# NES_IO_US_SNES_REV1_5.net
KiCad netlist of a schematic drawn in EAGLE
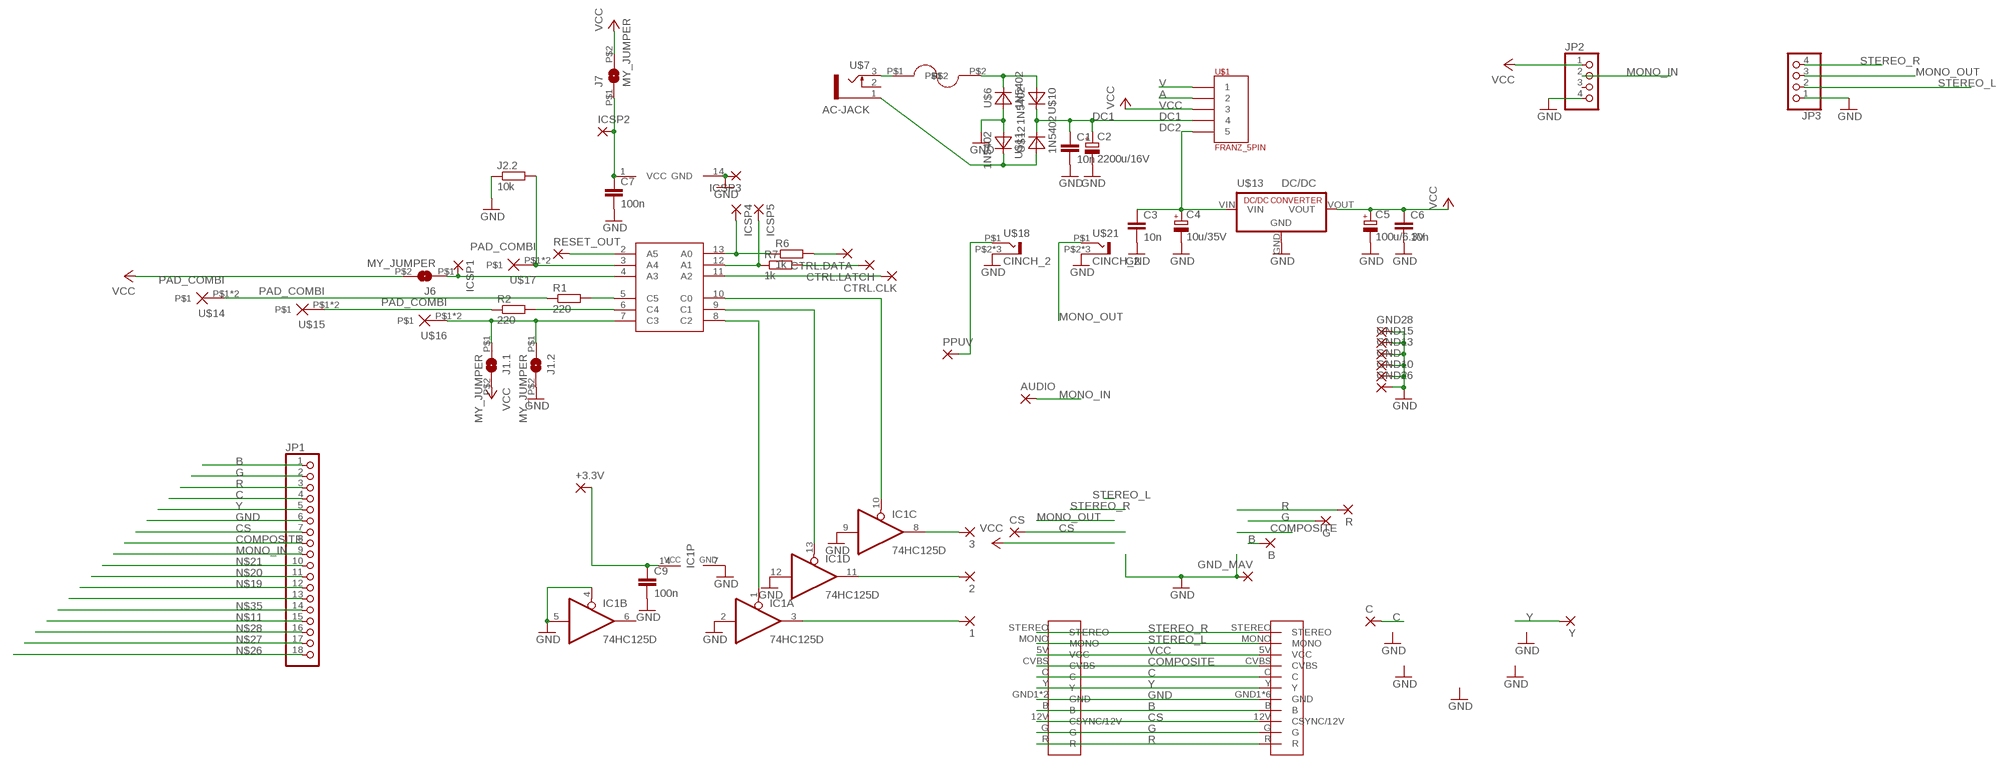
[diagram p0: schematic, sheet 1]

(export (version "E")
  (design (tool "Eeschema 10.0.6"))
  (components
    (comp (ref "+3.3V")
      (value "SMD2")
      (footprint "eagle-import:SMD1,27-2,54")
      (libsource (lib "eagle-import") (part "SMD2"))
    )
    (comp (ref "1")
      (value "SMD2")
      (footprint "eagle-import:SMD1,27-2,54")
      (libsource (lib "eagle-import") (part "SMD2"))
    )
    (comp (ref "2")
      (value "SMD2")
      (footprint "eagle-import:SMD1,27-2,54")
      (libsource (lib "eagle-import") (part "SMD2"))
    )
    (comp (ref "3")
      (value "SMD2")
      (footprint "eagle-import:SMD1,27-2,54")
      (libsource (lib "eagle-import") (part "SMD2"))
    )
    (comp (ref "AUDIO")
      (value "SMD2")
      (footprint "eagle-import:SMD1,27-2,54")
      (libsource (lib "eagle-import") (part "SMD2"))
    )
    (comp (ref "B")
      (value "SMD2")
      (footprint "eagle-import:SMD1,27-2,54")
      (libsource (lib "eagle-import") (part "SMD2"))
    )
    (comp (ref "C")
      (value "SMD2")
      (footprint "eagle-import:SMD1,27-2,54")
      (libsource (lib "eagle-import") (part "SMD2"))
    )
    (comp (ref "C1")
      (value "10n")
      (footprint "eagle-import:Z0805")
      (libsource (lib "eagle-import") (part "C0805"))
    )
    (comp (ref "C2")
      (value "2200u/16V")
      (footprint "eagle-import:E5-13")
      (libsource (lib "eagle-import") (part "resistor_CPOL-EUE5-13"))
    )
    (comp (ref "C3")
      (value "10n")
      (footprint "eagle-import:Z0805")
      (libsource (lib "eagle-import") (part "C0805"))
    )
    (comp (ref "C4")
      (value "10u/35V")
      (footprint "eagle-import:PANASONIC_B")
      (libsource (lib "eagle-import") (part "CPOL-EUB"))
    )
    (comp (ref "C5")
      (value "100u/6.3V")
      (footprint "eagle-import:PANASONIC_D")
      (libsource (lib "eagle-import") (part "CPOL-EUD"))
    )
    (comp (ref "C6")
      (value "10n")
      (footprint "eagle-import:Z0805")
      (libsource (lib "eagle-import") (part "C0805"))
    )
    (comp (ref "C7")
      (value "100n")
      (footprint "eagle-import:Z0805")
      (libsource (lib "eagle-import") (part "C0805"))
    )
    (comp (ref "C9")
      (value "100n")
      (footprint "eagle-import:Z0805")
      (libsource (lib "eagle-import") (part "C0805"))
    )
    (comp (ref "CS")
      (value "SMD2")
      (footprint "eagle-import:SMD1,27-2,54")
      (libsource (lib "eagle-import") (part "SMD2"))
    )
    (comp (ref "CTRL.CLK")
      (value "SMD2")
      (footprint "eagle-import:SMD1,27-2,54")
      (libsource (lib "eagle-import") (part "SMD2"))
    )
    (comp (ref "CTRL.DATA")
      (value "SMD2")
      (footprint "eagle-import:SMD1,27-2,54")
      (libsource (lib "eagle-import") (part "SMD2"))
    )
    (comp (ref "CTRL.LATCH")
      (value "SMD2")
      (footprint "eagle-import:SMD1,27-2,54")
      (libsource (lib "eagle-import") (part "SMD2"))
    )
    (comp (ref "G")
      (value "SMD2")
      (footprint "eagle-import:SMD1,27-2,54")
      (libsource (lib "eagle-import") (part "SMD2"))
    )
    (comp (ref "GND")
      (value "SMD5")
      (footprint "eagle-import:SMD2,54-5,08")
      (libsource (lib "eagle-import") (part "SMD5"))
    )
    (comp (ref "GND10")
      (value "SMD5")
      (footprint "eagle-import:SMD2,54-5,08")
      (libsource (lib "eagle-import") (part "SMD5"))
    )
    (comp (ref "GND13")
      (value "SMD5")
      (footprint "eagle-import:SMD2,54-5,08")
      (libsource (lib "eagle-import") (part "SMD5"))
    )
    (comp (ref "GND15")
      (value "SMD5")
      (footprint "eagle-import:SMD2,54-5,08")
      (libsource (lib "eagle-import") (part "SMD5"))
    )
    (comp (ref "GND26")
      (value "SMD5")
      (footprint "eagle-import:SMD2,54-5,08")
      (libsource (lib "eagle-import") (part "SMD5"))
    )
    (comp (ref "GND28")
      (value "SMD5")
      (footprint "eagle-import:SMD2,54-5,08")
      (libsource (lib "eagle-import") (part "SMD5"))
    )
    (comp (ref "GND_MAV")
      (value "SMD2")
      (footprint "eagle-import:SMD1,27-2,54")
      (libsource (lib "eagle-import") (part "SMD2"))
    )
    (comp (ref "IC1")
      (value "74HC125D")
      (footprint "eagle-import:SO14")
      (libsource (lib "eagle-import") (part "74125DHC"))
    )
    (comp (ref "ICSP1")
      (value "1,6/0,8")
      (footprint "eagle-import:1,6_0,8")
      (libsource (lib "eagle-import") (part "1,6/0,8"))
    )
    (comp (ref "ICSP2")
      (value "1,6/0,8")
      (footprint "eagle-import:1,6_0,8")
      (libsource (lib "eagle-import") (part "1,6/0,8"))
    )
    (comp (ref "ICSP3")
      (value "1,6/0,8")
      (footprint "eagle-import:1,6_0,8")
      (libsource (lib "eagle-import") (part "1,6/0,8"))
    )
    (comp (ref "ICSP4")
      (value "1,6/0,8")
      (footprint "eagle-import:1,6_0,8")
      (libsource (lib "eagle-import") (part "1,6/0,8"))
    )
    (comp (ref "ICSP5")
      (value "1,6/0,8")
      (footprint "eagle-import:1,6_0,8")
      (libsource (lib "eagle-import") (part "1,6/0,8"))
    )
    (comp (ref "J1.1")
      (value "MY_JUMPER")
      (footprint "eagle-import:MYJUMP")
      (libsource (lib "eagle-import") (part "MY_JUMPER"))
    )
    (comp (ref "J1.2")
      (value "MY_JUMPER")
      (footprint "eagle-import:MYJUMP")
      (libsource (lib "eagle-import") (part "MY_JUMPER"))
    )
    (comp (ref "J2.2")
      (value "10k")
      (footprint "eagle-import:Z0805")
      (libsource (lib "eagle-import") (part "R0805"))
    )
    (comp (ref "J6")
      (value "MY_JUMPER")
      (footprint "eagle-import:MYJUMP")
      (libsource (lib "eagle-import") (part "MY_JUMPER"))
    )
    (comp (ref "J7")
      (value "MY_JUMPER")
      (footprint "eagle-import:MYJUMP")
      (libsource (lib "eagle-import") (part "MY_JUMPER"))
    )
    (comp (ref "JP1")
      (value "PINHD-1X18_2.00")
      (footprint "eagle-import:1X18M")
      (libsource (lib "eagle-import") (part "PINHD-1X18_2.00"))
    )
    (comp (ref "JP2")
      (value "PINHD-1X04_2.54-S")
      (footprint "eagle-import:1X04-S")
      (libsource (lib "eagle-import") (part "PINHD-1X04_2.54-S"))
    )
    (comp (ref "JP3")
      (value "PINHD-1X04_2.54-S")
      (footprint "eagle-import:1X04-S")
      (libsource (lib "eagle-import") (part "PINHD-1X04_2.54-S"))
    )
    (comp (ref "PPUV")
      (value "SMD2")
      (footprint "eagle-import:SMD1,27-2,54")
      (libsource (lib "eagle-import") (part "SMD2"))
    )
    (comp (ref "R")
      (value "SMD2")
      (footprint "eagle-import:SMD1,27-2,54")
      (libsource (lib "eagle-import") (part "SMD2"))
    )
    (comp (ref "R1")
      (value "220")
      (footprint "eagle-import:Z0805")
      (libsource (lib "eagle-import") (part "R0805"))
    )
    (comp (ref "R2")
      (value "220")
      (footprint "eagle-import:Z0805")
      (libsource (lib "eagle-import") (part "R0805"))
    )
    (comp (ref "R6")
      (value "1k")
      (footprint "eagle-import:Z0805")
      (libsource (lib "eagle-import") (part "R0805"))
    )
    (comp (ref "R7")
      (value "1k")
      (footprint "eagle-import:Z0805")
      (libsource (lib "eagle-import") (part "R0805"))
    )
    (comp (ref "RESET_OUT")
      (value "SMD2")
      (footprint "eagle-import:SMD1,27-2,54")
      (libsource (lib "eagle-import") (part "SMD2"))
    )
    (comp (ref "U$1")
      (value "FRANZ_5PIN")
      (footprint "eagle-import:5X2.22RM4")
      (libsource (lib "eagle-import") (part "FRANZ_5PIN"))
    )
    (comp (ref "U$2")
      (value "FUSEHOLDER")
      (footprint "eagle-import:FUSEHOLDER")
      (libsource (lib "eagle-import") (part "FUSEHOLDER"))
    )
    (comp (ref "U$5")
      (value "PIC16F630_SIMPLE")
      (footprint "eagle-import:PIC16F630")
      (libsource (lib "eagle-import") (part "PIC16F630_SIMPLE"))
    )
    (comp (ref "U$6")
      (value "1N5402")
      (footprint "eagle-import:DO201")
      (libsource (lib "eagle-import") (part "1N5402"))
    )
    (comp (ref "U$7")
      (value "AC-JACK")
      (footprint "eagle-import:AC-JACK")
      (libsource (lib "eagle-import") (part "AC-JACK"))
    )
    (comp (ref "U$10")
      (value "1N5402")
      (footprint "eagle-import:DO201")
      (libsource (lib "eagle-import") (part "1N5402"))
    )
    (comp (ref "U$11")
      (value "1N5402")
      (footprint "eagle-import:DO201")
      (libsource (lib "eagle-import") (part "1N5402"))
    )
    (comp (ref "U$12")
      (value "1N5402")
      (footprint "eagle-import:DO201")
      (libsource (lib "eagle-import") (part "1N5402"))
    )
    (comp (ref "U$13")
      (value "DC/DC")
      (footprint "eagle-import:RECOM")
      (libsource (lib "eagle-import") (part "DC/DC"))
    )
    (comp (ref "U$14")
      (value "PAD_COMBI")
      (footprint "eagle-import:PAD_COMBI")
      (libsource (lib "eagle-import") (part "PAD_COMBI"))
    )
    (comp (ref "U$15")
      (value "PAD_COMBI")
      (footprint "eagle-import:PAD_COMBI")
      (libsource (lib "eagle-import") (part "PAD_COMBI"))
    )
    (comp (ref "U$16")
      (value "PAD_COMBI")
      (footprint "eagle-import:PAD_COMBI")
      (libsource (lib "eagle-import") (part "PAD_COMBI"))
    )
    (comp (ref "U$17")
      (value "PAD_COMBI")
      (footprint "eagle-import:PAD_COMBI")
      (libsource (lib "eagle-import") (part "PAD_COMBI"))
    )
    (comp (ref "U$18")
      (value "CINCH_2")
      (footprint "eagle-import:CINCH_2")
      (libsource (lib "eagle-import") (part "CINCH_2"))
    )
    (comp (ref "U$19")
      (value "GC-MULTIAV")
      (footprint "eagle-import:GC-MULTIAV")
      (libsource (lib "eagle-import") (part "GC-MULTIAV"))
    )
    (comp (ref "U$20")
      (value "SNES-MULTIAV2")
      (footprint "eagle-import:SNES-MULTIAV2")
      (libsource (lib "eagle-import") (part "SNES-MULTIAV2"))
    )
    (comp (ref "U$21")
      (value "CINCH_2")
      (footprint "eagle-import:CINCH_2")
      (libsource (lib "eagle-import") (part "CINCH_2"))
    )
    (comp (ref "Y")
      (value "SMD2")
      (footprint "eagle-import:SMD1,27-2,54")
      (libsource (lib "eagle-import") (part "SMD2"))
    )
  )
  (nets
    (net (code "1") (name "/A") (class "Default")
      (node (ref "U$1") (pin "P$2") (pinfunction "2_P$2") (pintype "bidirectional"))
    )
    (net (code "2") (name "/B") (class "Default")
      (node (ref "B") (pin "1") (pinfunction "P_1") (pintype "passive"))
      (node (ref "JP1") (pin "1") (pinfunction "1_1") (pintype "passive"))
      (node (ref "U$19") (pin "B") (pinfunction "B_B") (pintype "output"))
      (node (ref "U$20") (pin "B") (pinfunction "B_B") (pintype "output"))
    )
    (net (code "3") (name "/C") (class "Default")
      (node (ref "C") (pin "1") (pinfunction "P_1") (pintype "passive"))
      (node (ref "JP1") (pin "4") (pinfunction "4_4") (pintype "passive"))
      (node (ref "U$19") (pin "C") (pinfunction "C_C") (pintype "output"))
      (node (ref "U$20") (pin "C") (pinfunction "C_C") (pintype "output"))
    )
    (net (code "4") (name "/COMPOSITE") (class "Default")
      (node (ref "JP1") (pin "8") (pinfunction "8_8") (pintype "passive"))
      (node (ref "PPUV") (pin "1") (pinfunction "P_1") (pintype "passive"))
      (node (ref "U$18") (pin "P$1") (pinfunction "T_P$1") (pintype "passive"))
      (node (ref "U$19") (pin "CVBS") (pinfunction "CVBS_CVBS") (pintype "output"))
      (node (ref "U$20") (pin "CVBS") (pinfunction "CVBS_CVBS") (pintype "output"))
    )
    (net (code "5") (name "/CS") (class "Default")
      (node (ref "CS") (pin "1") (pinfunction "P_1") (pintype "passive"))
      (node (ref "JP1") (pin "7") (pinfunction "7_7") (pintype "passive"))
      (node (ref "U$19") (pin "12V") (pinfunction "CSYNC/12V_12V") (pintype "output"))
      (node (ref "U$20") (pin "12V") (pinfunction "CSYNC/12V_12V") (pintype "output"))
    )
    (net (code "6") (name "/DC1") (class "Default")
      (node (ref "C1") (pin "1") (pinfunction "1_1") (pintype "passive"))
      (node (ref "C2") (pin "+") (pinfunction "+_+") (pintype "passive"))
      (node (ref "U$1") (pin "P$4") (pinfunction "4_P$4") (pintype "bidirectional"))
      (node (ref "U$10") (pin "C") (pinfunction "C_C") (pintype "passive"))
      (node (ref "U$12") (pin "C") (pinfunction "C_C") (pintype "passive"))
    )
    (net (code "7") (name "/DC2") (class "Default")
      (node (ref "C3") (pin "1") (pinfunction "1_1") (pintype "passive"))
      (node (ref "C4") (pin "+") (pinfunction "+_+") (pintype "passive"))
      (node (ref "U$1") (pin "P$5") (pinfunction "5_P$5") (pintype "bidirectional"))
      (node (ref "U$13") (pin "VIN") (pinfunction "VIN_VIN") (pintype "passive"))
    )
    (net (code "8") (name "/G") (class "Default")
      (node (ref "G") (pin "1") (pinfunction "P_1") (pintype "passive"))
      (node (ref "JP1") (pin "2") (pinfunction "2_2") (pintype "passive"))
      (node (ref "U$19") (pin "G") (pinfunction "G_G") (pintype "output"))
      (node (ref "U$20") (pin "G") (pinfunction "G_G") (pintype "output"))
    )
    (net (code "9") (name "/MONO_IN") (class "Default")
      (node (ref "AUDIO") (pin "1") (pinfunction "P_1") (pintype "passive"))
      (node (ref "JP1") (pin "9") (pinfunction "9_9") (pintype "passive"))
      (node (ref "JP2") (pin "2") (pinfunction "2_2") (pintype "passive"))
    )
    (net (code "10") (name "/MONO_OUT") (class "Default")
      (node (ref "JP3") (pin "3") (pinfunction "3_3") (pintype "passive"))
      (node (ref "U$21") (pin "P$1") (pinfunction "T_P$1") (pintype "passive"))
    )
    (net (code "11") (name "/N$11") (class "Default")
      (node (ref "3") (pin "1") (pinfunction "P_1") (pintype "passive"))
      (node (ref "IC1") (pin "8") (pinfunction "O_8") (pintype "tri_state"))
      (node (ref "JP1") (pin "15") (pinfunction "15_15") (pintype "passive"))
    )
    (net (code "12") (name "/N$19") (class "Default")
      (node (ref "CTRL.DATA") (pin "1") (pinfunction "P_1") (pintype "passive"))
      (node (ref "JP1") (pin "12") (pinfunction "12_12") (pintype "passive"))
      (node (ref "R6") (pin "2") (pinfunction "2_2") (pintype "passive"))
    )
    (net (code "13") (name "/N$20") (class "Default")
      (node (ref "CTRL.LATCH") (pin "1") (pinfunction "P_1") (pintype "passive"))
      (node (ref "JP1") (pin "11") (pinfunction "11_11") (pintype "passive"))
      (node (ref "R7") (pin "2") (pinfunction "2_2") (pintype "passive"))
    )
    (net (code "14") (name "/N$21") (class "Default")
      (node (ref "CTRL.CLK") (pin "1") (pinfunction "P_1") (pintype "passive"))
      (node (ref "JP1") (pin "10") (pinfunction "10_10") (pintype "passive"))
      (node (ref "U$5") (pin "11") (pinfunction "A2_11") (pintype "bidirectional"))
    )
    (net (code "15") (name "/N$26") (class "Default")
      (node (ref "+3.3V") (pin "1") (pinfunction "P_1") (pintype "passive"))
      (node (ref "C9") (pin "1") (pinfunction "1_1") (pintype "passive"))
      (node (ref "IC1") (pin "14") (pinfunction "VCC_14") (pintype "power_in"))
      (node (ref "JP1") (pin "18") (pinfunction "18_18") (pintype "passive"))
    )
    (net (code "16") (name "/N$27") (class "Default")
      (node (ref "1") (pin "1") (pinfunction "P_1") (pintype "passive"))
      (node (ref "IC1") (pin "3") (pinfunction "O_3") (pintype "tri_state"))
      (node (ref "JP1") (pin "17") (pinfunction "17_17") (pintype "passive"))
    )
    (net (code "17") (name "/N$28") (class "Default")
      (node (ref "2") (pin "1") (pinfunction "P_1") (pintype "passive"))
      (node (ref "IC1") (pin "11") (pinfunction "O_11") (pintype "tri_state"))
      (node (ref "JP1") (pin "16") (pinfunction "16_16") (pintype "passive"))
    )
    (net (code "18") (name "/N$35") (class "Default")
      (node (ref "JP1") (pin "14") (pinfunction "14_14") (pintype "passive"))
      (node (ref "RESET_OUT") (pin "1") (pinfunction "P_1") (pintype "passive"))
      (node (ref "U$5") (pin "2") (pinfunction "A5_2") (pintype "bidirectional"))
    )
    (net (code "19") (name "/R") (class "Default")
      (node (ref "JP1") (pin "3") (pinfunction "3_3") (pintype "passive"))
      (node (ref "R") (pin "1") (pinfunction "P_1") (pintype "passive"))
      (node (ref "U$19") (pin "R") (pinfunction "R_R") (pintype "output"))
      (node (ref "U$20") (pin "R") (pinfunction "R_R") (pintype "output"))
    )
    (net (code "20") (name "/STEREO_L") (class "Default")
      (node (ref "JP3") (pin "2") (pinfunction "2_2") (pintype "passive"))
      (node (ref "U$19") (pin "MONO") (pinfunction "MONO_MONO") (pintype "output"))
      (node (ref "U$20") (pin "MONO") (pinfunction "MONO_MONO") (pintype "output"))
    )
    (net (code "21") (name "/STEREO_R") (class "Default")
      (node (ref "JP3") (pin "4") (pinfunction "4_4") (pintype "passive"))
      (node (ref "U$19") (pin "STEREO") (pinfunction "STEREO_STEREO") (pintype "output"))
      (node (ref "U$20") (pin "STEREO") (pinfunction "STEREO_STEREO") (pintype "output"))
    )
    (net (code "22") (name "/V") (class "Default")
      (node (ref "U$1") (pin "P$1") (pinfunction "1_P$1") (pintype "bidirectional"))
    )
    (net (code "23") (name "/Y") (class "Default")
      (node (ref "JP1") (pin "5") (pinfunction "5_5") (pintype "passive"))
      (node (ref "U$19") (pin "Y") (pinfunction "Y_Y") (pintype "output"))
      (node (ref "U$20") (pin "Y") (pinfunction "Y_Y") (pintype "output"))
      (node (ref "Y") (pin "1") (pinfunction "P_1") (pintype "passive"))
    )
    (net (code "24") (name "GND") (class "Default")
      (node (ref "C1") (pin "2") (pinfunction "2_2") (pintype "passive"))
      (node (ref "C2") (pin "-") (pinfunction "-_-") (pintype "passive"))
      (node (ref "C3") (pin "2") (pinfunction "2_2") (pintype "passive"))
      (node (ref "C4") (pin "-") (pinfunction "-_-") (pintype "passive"))
      (node (ref "C5") (pin "-") (pinfunction "-_-") (pintype "passive"))
      (node (ref "C6") (pin "2") (pinfunction "2_2") (pintype "passive"))
      (node (ref "C7") (pin "2") (pinfunction "2_2") (pintype "passive"))
      (node (ref "C9") (pin "2") (pinfunction "2_2") (pintype "passive"))
      (node (ref "GND") (pin "1") (pinfunction "P_1") (pintype "passive"))
      (node (ref "GND10") (pin "1") (pinfunction "P_1") (pintype "passive"))
      (node (ref "GND13") (pin "1") (pinfunction "P_1") (pintype "passive"))
      (node (ref "GND15") (pin "1") (pinfunction "P_1") (pintype "passive"))
      (node (ref "GND26") (pin "1") (pinfunction "P_1") (pintype "passive"))
      (node (ref "GND28") (pin "1") (pinfunction "P_1") (pintype "passive"))
      (node (ref "GND_MAV") (pin "1") (pinfunction "P_1") (pintype "passive"))
      (node (ref "IC1") (pin "12") (pinfunction "I_12") (pintype "input"))
      (node (ref "IC1") (pin "2") (pinfunction "I_2") (pintype "input"))
      (node (ref "IC1") (pin "4") (pinfunction "OE_4") (pintype "input"))
      (node (ref "IC1") (pin "5") (pinfunction "I_5") (pintype "input"))
      (node (ref "IC1") (pin "7") (pinfunction "GND_7") (pintype "power_in"))
      (node (ref "IC1") (pin "9") (pinfunction "I_9") (pintype "input"))
      (node (ref "ICSP3") (pin "1") (pinfunction "P_1") (pintype "passive"))
      (node (ref "J1.2") (pin "P$2") (pinfunction "2_P$2") (pintype "passive"))
      (node (ref "J2.2") (pin "1") (pinfunction "1_1") (pintype "passive"))
      (node (ref "JP1") (pin "6") (pinfunction "6_6") (pintype "passive"))
      (node (ref "JP2") (pin "4") (pinfunction "4_4") (pintype "passive"))
      (node (ref "JP3") (pin "1") (pinfunction "1_1") (pintype "passive"))
      (node (ref "U$11") (pin "A") (pinfunction "A_A") (pintype "passive"))
      (node (ref "U$13") (pin "GND") (pinfunction "GND_GND") (pintype "passive"))
      (node (ref "U$18") (pin "P$2") (pinfunction "S_P$2") (pintype "passive"))
      (node (ref "U$18") (pin "P$3") (pinfunction "S_P$3") (pintype "passive"))
      (node (ref "U$18") (pin "P$4") (pinfunction "S_P$4") (pintype "passive"))
      (node (ref "U$19") (pin "GND1") (pinfunction "GND_GND1") (pintype "output"))
      (node (ref "U$19") (pin "GND2") (pinfunction "GND_GND2") (pintype "output"))
      (node (ref "U$19") (pin "GND3") (pinfunction "GND_GND3") (pintype "output"))
      (node (ref "U$19") (pin "GND4") (pinfunction "GND_GND4") (pintype "output"))
      (node (ref "U$19") (pin "GND5") (pinfunction "GND_GND5") (pintype "output"))
      (node (ref "U$19") (pin "GND6") (pinfunction "GND_GND6") (pintype "output"))
      (node (ref "U$20") (pin "GND1") (pinfunction "GND_GND1") (pintype "output"))
      (node (ref "U$20") (pin "GND2") (pinfunction "GND_GND2") (pintype "output"))
      (node (ref "U$21") (pin "P$2") (pinfunction "S_P$2") (pintype "passive"))
      (node (ref "U$21") (pin "P$3") (pinfunction "S_P$3") (pintype "passive"))
      (node (ref "U$21") (pin "P$4") (pinfunction "S_P$4") (pintype "passive"))
      (node (ref "U$5") (pin "14") (pinfunction "GND_14") (pintype "bidirectional"))
      (node (ref "U$6") (pin "A") (pinfunction "A_A") (pintype "passive"))
    )
    (net (code "25") (name "Net-(IC1A-OE)") (class "Default")
      (node (ref "IC1") (pin "1") (pinfunction "OE_1") (pintype "input"))
      (node (ref "U$5") (pin "8") (pinfunction "C2_8") (pintype "bidirectional"))
    )
    (net (code "26") (name "Net-(IC1C-OE)") (class "Default")
      (node (ref "IC1") (pin "10") (pinfunction "OE_10") (pintype "input"))
      (node (ref "U$5") (pin "10") (pinfunction "C0_10") (pintype "bidirectional"))
    )
    (net (code "27") (name "Net-(IC1D-OE)") (class "Default")
      (node (ref "IC1") (pin "13") (pinfunction "OE_13") (pintype "input"))
      (node (ref "U$5") (pin "9") (pinfunction "C1_9") (pintype "bidirectional"))
    )
    (net (code "28") (name "Net-(ICSP1-P)") (class "Default")
      (node (ref "ICSP1") (pin "1") (pinfunction "P_1") (pintype "passive"))
      (node (ref "J6") (pin "P$1") (pinfunction "1_P$1") (pintype "passive"))
      (node (ref "U$5") (pin "4") (pinfunction "A3_4") (pintype "bidirectional"))
    )
    (net (code "29") (name "Net-(ICSP2-P)") (class "Default")
      (node (ref "C7") (pin "1") (pinfunction "1_1") (pintype "passive"))
      (node (ref "ICSP2") (pin "1") (pinfunction "P_1") (pintype "passive"))
      (node (ref "J7") (pin "P$1") (pinfunction "1_P$1") (pintype "passive"))
      (node (ref "U$5") (pin "1") (pinfunction "VCC_1") (pintype "bidirectional"))
    )
    (net (code "30") (name "Net-(ICSP4-P)") (class "Default")
      (node (ref "ICSP4") (pin "1") (pinfunction "P_1") (pintype "passive"))
      (node (ref "R6") (pin "1") (pinfunction "1_1") (pintype "passive"))
      (node (ref "U$5") (pin "13") (pinfunction "A0_13") (pintype "bidirectional"))
    )
    (net (code "31") (name "Net-(ICSP5-P)") (class "Default")
      (node (ref "ICSP5") (pin "1") (pinfunction "P_1") (pintype "passive"))
      (node (ref "R7") (pin "1") (pinfunction "1_1") (pintype "passive"))
      (node (ref "U$5") (pin "12") (pinfunction "A1_12") (pintype "bidirectional"))
    )
    (net (code "32") (name "Net-(J1.1-1)") (class "Default")
      (node (ref "J1.1") (pin "P$1") (pinfunction "1_P$1") (pintype "passive"))
      (node (ref "J1.2") (pin "P$1") (pinfunction "1_P$1") (pintype "passive"))
      (node (ref "U$16") (pin "P$1") (pinfunction "P$1_P$1") (pintype "bidirectional"))
      (node (ref "U$16") (pin "P$2") (pinfunction "P$1_P$2") (pintype "bidirectional"))
      (node (ref "U$5") (pin "7") (pinfunction "C3_7") (pintype "bidirectional"))
    )
    (net (code "33") (name "Net-(R1-Pad1)") (class "Default")
      (node (ref "R1") (pin "1") (pinfunction "1_1") (pintype "passive"))
      (node (ref "U$14") (pin "P$1") (pinfunction "P$1_P$1") (pintype "bidirectional"))
      (node (ref "U$14") (pin "P$2") (pinfunction "P$1_P$2") (pintype "bidirectional"))
    )
    (net (code "34") (name "Net-(R2-Pad1)") (class "Default")
      (node (ref "R2") (pin "1") (pinfunction "1_1") (pintype "passive"))
      (node (ref "U$15") (pin "P$1") (pinfunction "P$1_P$1") (pintype "bidirectional"))
      (node (ref "U$15") (pin "P$2") (pinfunction "P$1_P$2") (pintype "bidirectional"))
    )
    (net (code "35") (name "Net-(U$2-PadP$1)") (class "Default")
      (node (ref "U$2") (pin "P$1") (pinfunction "P$1_P$1") (pintype "bidirectional"))
      (node (ref "U$7") (pin "3") (pinfunction "3_3") (pintype "passive"))
    )
    (net (code "36") (name "Net-(U$5A-A4)") (class "Default")
      (node (ref "J2.2") (pin "2") (pinfunction "2_2") (pintype "passive"))
      (node (ref "U$17") (pin "P$1") (pinfunction "P$1_P$1") (pintype "bidirectional"))
      (node (ref "U$17") (pin "P$2") (pinfunction "P$1_P$2") (pintype "bidirectional"))
      (node (ref "U$5") (pin "3") (pinfunction "A4_3") (pintype "bidirectional"))
    )
    (net (code "37") (name "Net-(U$5A-C4)") (class "Default")
      (node (ref "R2") (pin "2") (pinfunction "2_2") (pintype "passive"))
      (node (ref "U$5") (pin "6") (pinfunction "C4_6") (pintype "bidirectional"))
    )
    (net (code "38") (name "Net-(U$5A-C5)") (class "Default")
      (node (ref "R1") (pin "2") (pinfunction "2_2") (pintype "passive"))
      (node (ref "U$5") (pin "5") (pinfunction "C5_5") (pintype "bidirectional"))
    )
    (net (code "39") (name "Net-(U$7-5)") (class "Default")
      (node (ref "U$11") (pin "C") (pinfunction "C_C") (pintype "passive"))
      (node (ref "U$12") (pin "A") (pinfunction "A_A") (pintype "passive"))
      (node (ref "U$7") (pin "1") (pinfunction "5_1") (pintype "passive"))
    )
    (net (code "40") (name "Net-(U$10-PadA)") (class "Default")
      (node (ref "U$10") (pin "A") (pinfunction "A_A") (pintype "passive"))
      (node (ref "U$2") (pin "P$2") (pinfunction "P$2_P$2") (pintype "bidirectional"))
      (node (ref "U$6") (pin "C") (pinfunction "C_C") (pintype "passive"))
    )
    (net (code "41") (name "VCC") (class "Default")
      (node (ref "C5") (pin "+") (pinfunction "+_+") (pintype "passive"))
      (node (ref "C6") (pin "1") (pinfunction "1_1") (pintype "passive"))
      (node (ref "J1.1") (pin "P$2") (pinfunction "2_P$2") (pintype "passive"))
      (node (ref "J6") (pin "P$2") (pinfunction "2_P$2") (pintype "passive"))
      (node (ref "J7") (pin "P$2") (pinfunction "2_P$2") (pintype "passive"))
      (node (ref "JP2") (pin "1") (pinfunction "1_1") (pintype "passive"))
      (node (ref "U$1") (pin "P$3") (pinfunction "3_P$3") (pintype "bidirectional"))
      (node (ref "U$13") (pin "VOUT") (pinfunction "VOUT_VOUT") (pintype "passive"))
      (node (ref "U$19") (pin "5V") (pinfunction "VCC_5V") (pintype "output"))
      (node (ref "U$20") (pin "5V") (pinfunction "VCC_5V") (pintype "output"))
    )
    (net (code "42") (name "unconnected-(IC1B-O-Pad6)") (class "Default")
      (node (ref "IC1") (pin "6") (pinfunction "O_6") (pintype "tri_state"))
    )
    (net (code "43") (name "unconnected-(JP1-Pad13)") (class "Default")
      (node (ref "JP1") (pin "13") (pinfunction "13_13") (pintype "passive"))
    )
    (net (code "44") (name "unconnected-(JP2-Pad3)") (class "Default")
      (node (ref "JP2") (pin "3") (pinfunction "3_3") (pintype "passive"))
    )
    (net (code "45") (name "unconnected-(U$7-4-Pad2)") (class "Default")
      (node (ref "U$7") (pin "2") (pinfunction "4_2") (pintype "passive"))
    )
  )
)
